# v1_0.net
KiCad netlist of a schematic drawn in Altium Designer
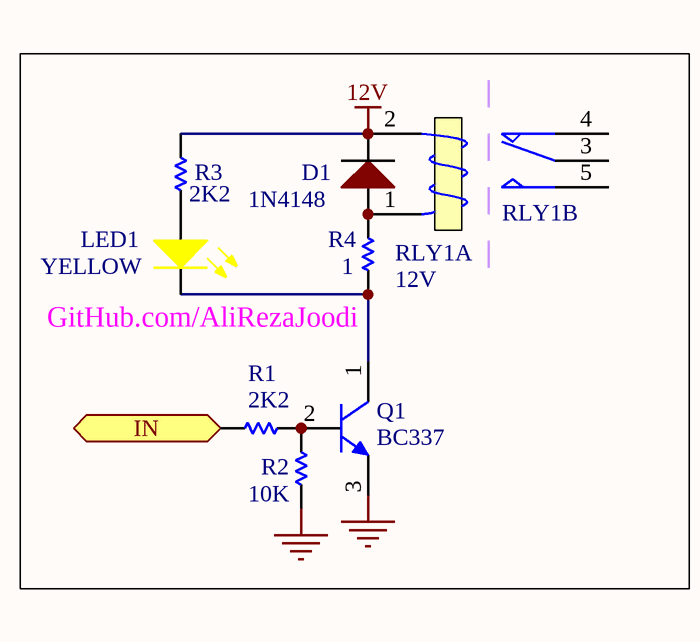
[diagram p0: v1.0.SchDoc]

(export (version "E")
  (design (tool "Eeschema 10.0.6"))
  (components
    (comp (ref "D1")
      (value "1N4148")
      (footprint "D_THD_AXIAL0.3_DO-35")
      (description "Diode,")
      (libsource (lib "Passive") (part "Diode_2Form"))
    )
    (comp (ref "LED1")
      (value "YELLOW")
      (footprint "LED_THD_3MM_YELLOW_R")
      (description "LED, Yellow")
      (fields (field (name "MANUFACTURER") "Generic Components") (field (name "PUBLISHER") "Altium Limited"))
      (libsource (lib "Display") (part "LED_YELLOW"))
    )
    (comp (ref "Q1")
      (value "BC337")
      (footprint "TO92C")
      (description "NPN Bipolar Transistor")
      (fields (field (name "MANUFACTURER") "Generic Components") (field (name "PUBLISHER") "Altium Limited"))
      (libsource (lib "Miscellaneous Devices") (part "NPN"))
    )
    (comp (ref "R1")
      (value "2K2")
      (footprint "R_THD_AXIAL0.4(1/4W)")
      (description "Resistor")
      (libsource (lib "Passive") (part "Resistor"))
    )
    (comp (ref "R2")
      (value "10K")
      (footprint "R_THD_AXIAL0.4(1/4W)")
      (description "Resistor")
      (libsource (lib "Passive") (part "Resistor"))
    )
    (comp (ref "R3")
      (value "2K2")
      (footprint "R_THD_AXIAL0.4(1/4W)")
      (description "Resistor")
      (libsource (lib "Passive") (part "Resistor"))
    )
    (comp (ref "R4")
      (value "1")
      (footprint "R_THD_AXIAL0.4(1/4W)")
      (description "Resistor")
      (libsource (lib "Passive") (part "Resistor"))
    )
    (comp (ref "RLY1")
      (value "12V")
      (footprint "RELAY_SPDT_5PIN_2216")
      (description "SPDT Relay")
      (libsource (lib "Passive") (part "Relay_SPDT_2Form"))
    )
  )
  (nets
    (net (code "1") (name "/IN") (class "Default")
      (node (ref "R1") (pin "2") (pinfunction "2_2") (pintype "passive"))
    )
    (net (code "2") (name "12V") (class "Default")
      (node (ref "D1") (pin "2") (pinfunction "K_2") (pintype "passive"))
      (node (ref "R3") (pin "2") (pinfunction "2_2") (pintype "passive"))
      (node (ref "RLY1") (pin "2") (pinfunction "T1_2") (pintype "passive"))
    )
    (net (code "3") (name "GND") (class "Default")
      (node (ref "Q1") (pin "3") (pinfunction "E_3") (pintype "passive"))
      (node (ref "R2") (pin "1") (pinfunction "1_1") (pintype "passive"))
    )
    (net (code "4") (name "Net-(D1-A)") (class "Default")
      (node (ref "D1") (pin "1") (pinfunction "A_1") (pintype "passive"))
      (node (ref "R4") (pin "2") (pinfunction "2_2") (pintype "passive"))
      (node (ref "RLY1") (pin "1") (pinfunction "T2_1") (pintype "passive"))
    )
    (net (code "5") (name "Net-(LED1-A)") (class "Default")
      (node (ref "LED1") (pin "1") (pinfunction "A_1") (pintype "passive"))
      (node (ref "R3") (pin "1") (pinfunction "1_1") (pintype "passive"))
    )
    (net (code "6") (name "Net-(LED1-K)") (class "Default")
      (node (ref "LED1") (pin "2") (pinfunction "K_2") (pintype "passive"))
      (node (ref "Q1") (pin "1") (pinfunction "C_1") (pintype "passive"))
      (node (ref "R4") (pin "1") (pinfunction "1_1") (pintype "passive"))
    )
    (net (code "7") (name "Net-(Q1-B)") (class "Default")
      (node (ref "Q1") (pin "2") (pinfunction "B_2") (pintype "passive"))
      (node (ref "R1") (pin "1") (pinfunction "1_1") (pintype "passive"))
      (node (ref "R2") (pin "2") (pinfunction "2_2") (pintype "passive"))
    )
    (net (code "8") (name "unconnected-(RLY1B-COM-Pad3)") (class "Default")
      (node (ref "RLY1") (pin "3") (pinfunction "COM_3") (pintype "passive"))
    )
    (net (code "9") (name "unconnected-(RLY1B-NC-Pad4)") (class "Default")
      (node (ref "RLY1") (pin "4") (pinfunction "NC_4") (pintype "passive"))
    )
    (net (code "10") (name "unconnected-(RLY1B-NO-Pad5)") (class "Default")
      (node (ref "RLY1") (pin "5") (pinfunction "NO_5") (pintype "passive"))
    )
  )
)
